# Debug.net
KiCad netlist of a schematic drawn in Altium Designer
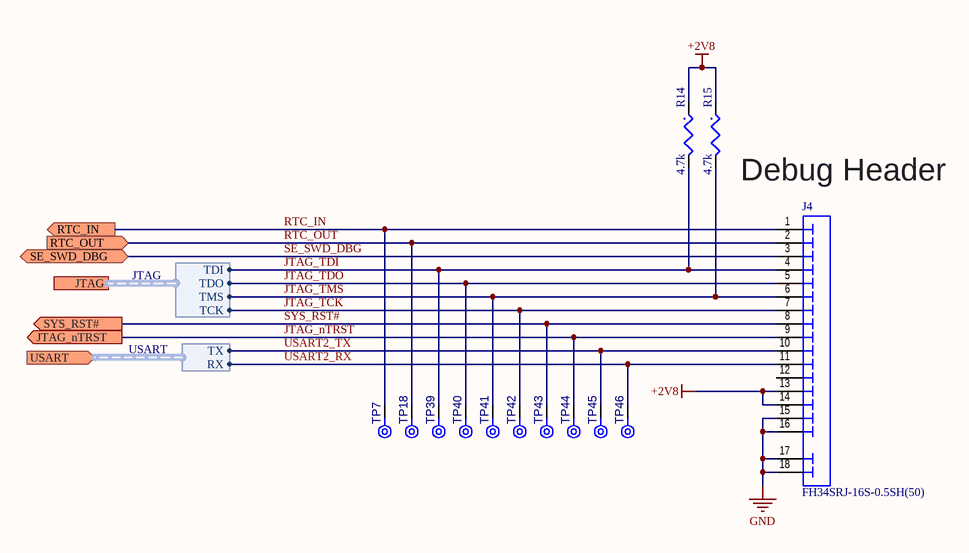
[diagram p0: Debug.SchDoc]

(export (version "E")
  (design (tool "Eeschema 10.0.6"))
  (components
    (comp (ref "J4")
      (value "FH34SRJ-16S-0.5SH(50)")
      (footprint "HIRO - FH34SRJ-16S-0.5SH_V")
      (libsource (lib "Altium Concord Pro on A365") (part "CN-FCC-16-2"))
    )
    (comp (ref "R14")
      (value "RES 4.7K 1/16W 1% 0402")
      (footprint "RESC0402(1005)_L")
      (description "4.7 kOhms ±1% 0.063W, 1/16W Chip Resistor 0402 (1005 Metric) Automotive AEC-Q200 Thick Film")
      (fields (field (name "RESISTANCE") "4.7k") (field (name "TOLERANCE") "1%"))
      (libsource (lib "Altium Concord Pro on A365") (part "RES-2"))
    )
    (comp (ref "R15")
      (value "RES 4.7K 1/16W 1% 0402")
      (footprint "RESC0402(1005)_L")
      (description "4.7 kOhms ±1% 0.063W, 1/16W Chip Resistor 0402 (1005 Metric) Automotive AEC-Q200 Thick Film")
      (fields (field (name "RESISTANCE") "4.7k") (field (name "TOLERANCE") "1%"))
      (libsource (lib "Altium Concord Pro on A365") (part "RES-2"))
    )
    (comp (ref "TP7")
      (value "TPAD8R")
      (footprint "TP08R")
      (description "0.8mm round")
      (libsource (lib "Altium Concord Pro on A365") (part "TP-R-1"))
    )
    (comp (ref "TP18")
      (value "TPAD8R")
      (footprint "TP08R")
      (description "0.8mm round")
      (libsource (lib "Altium Concord Pro on A365") (part "TP-R-1"))
    )
    (comp (ref "TP39")
      (value "TPAD8R")
      (footprint "TP08R")
      (description "0.8mm round")
      (libsource (lib "Altium Concord Pro on A365") (part "TP-R-1"))
    )
    (comp (ref "TP40")
      (value "TPAD8R")
      (footprint "TP08R")
      (description "0.8mm round")
      (libsource (lib "Altium Concord Pro on A365") (part "TP-R-1"))
    )
    (comp (ref "TP41")
      (value "TPAD8R")
      (footprint "TP08R")
      (description "0.8mm round")
      (libsource (lib "Altium Concord Pro on A365") (part "TP-R-1"))
    )
    (comp (ref "TP42")
      (value "TPAD8R")
      (footprint "TP08R")
      (description "0.8mm round")
      (libsource (lib "Altium Concord Pro on A365") (part "TP-R-1"))
    )
    (comp (ref "TP43")
      (value "TPAD8R")
      (footprint "TP08R")
      (description "0.8mm round")
      (libsource (lib "Altium Concord Pro on A365") (part "TP-R-1"))
    )
    (comp (ref "TP44")
      (value "TPAD8R")
      (footprint "TP08R")
      (description "0.8mm round")
      (libsource (lib "Altium Concord Pro on A365") (part "TP-R-1"))
    )
    (comp (ref "TP45")
      (value "TPAD8R")
      (footprint "TP08R")
      (description "0.8mm round")
      (libsource (lib "Altium Concord Pro on A365") (part "TP-R-1"))
    )
    (comp (ref "TP46")
      (value "TPAD8R")
      (footprint "TP08R")
      (description "0.8mm round")
      (libsource (lib "Altium Concord Pro on A365") (part "TP-R-1"))
    )
  )
  (nets
    (net (code "3") (name "+2V8") (class "Default")
      (node (ref "J4") (pin "13") (pinfunction "13_13") (pintype "passive"))
      (node (ref "J4") (pin "14") (pinfunction "14_14") (pintype "passive"))
      (node (ref "R14") (pin "1") (pinfunction "1_1") (pintype "passive"))
      (node (ref "R15") (pin "1") (pinfunction "1_1") (pintype "passive"))
    )
    (net (code "4") (name "/JTAG_TCK") (class "Default")
      (node (ref "J4") (pin "7") (pinfunction "7_7") (pintype "passive"))
      (node (ref "TP42") (pin "1") (pinfunction "TP_1") (pintype "passive"))
    )
    (net (code "5") (name "/JTAG_TDI") (class "Default")
      (node (ref "J4") (pin "4") (pinfunction "4_4") (pintype "passive"))
      (node (ref "R14") (pin "2") (pinfunction "2_2") (pintype "passive"))
      (node (ref "TP39") (pin "1") (pinfunction "TP_1") (pintype "passive"))
    )
    (net (code "6") (name "/JTAG_TDO") (class "Default")
      (node (ref "J4") (pin "5") (pinfunction "5_5") (pintype "passive"))
      (node (ref "TP40") (pin "1") (pinfunction "TP_1") (pintype "passive"))
    )
    (net (code "7") (name "/JTAG_TMS") (class "Default")
      (node (ref "J4") (pin "6") (pinfunction "6_6") (pintype "passive"))
      (node (ref "R15") (pin "2") (pinfunction "2_2") (pintype "passive"))
      (node (ref "TP41") (pin "1") (pinfunction "TP_1") (pintype "passive"))
    )
    (net (code "8") (name "/JTAG_nTRST") (class "Default")
      (node (ref "J4") (pin "9") (pinfunction "9_9") (pintype "passive"))
      (node (ref "TP44") (pin "1") (pinfunction "TP_1") (pintype "passive"))
    )
    (net (code "9") (name "/RTC_IN") (class "Default")
      (node (ref "J4") (pin "1") (pinfunction "1_1") (pintype "passive"))
      (node (ref "TP7") (pin "1") (pinfunction "TP_1") (pintype "passive"))
    )
    (net (code "10") (name "/RTC_OUT") (class "Default")
      (node (ref "J4") (pin "2") (pinfunction "2_2") (pintype "passive"))
      (node (ref "TP18") (pin "1") (pinfunction "TP_1") (pintype "passive"))
    )
    (net (code "11") (name "/SE_SWD_DBG") (class "Default")
      (node (ref "J4") (pin "3") (pinfunction "3_3") (pintype "passive"))
    )
    (net (code "12") (name "/SYS_RST#") (class "Default")
      (node (ref "J4") (pin "8") (pinfunction "8_8") (pintype "passive"))
      (node (ref "TP43") (pin "1") (pinfunction "TP_1") (pintype "passive"))
    )
    (net (code "13") (name "/USART2_RX") (class "Default")
      (node (ref "J4") (pin "11") (pinfunction "11_11") (pintype "passive"))
      (node (ref "TP46") (pin "1") (pinfunction "TP_1") (pintype "passive"))
    )
    (net (code "14") (name "/USART2_TX") (class "Default")
      (node (ref "J4") (pin "10") (pinfunction "10_10") (pintype "passive"))
      (node (ref "TP45") (pin "1") (pinfunction "TP_1") (pintype "passive"))
    )
    (net (code "17") (name "GND") (class "Default")
      (node (ref "J4") (pin "15") (pinfunction "15_15") (pintype "passive"))
      (node (ref "J4") (pin "16") (pinfunction "16_16") (pintype "passive"))
      (node (ref "J4") (pin "17") (pinfunction "17_17") (pintype "passive"))
      (node (ref "J4") (pin "18") (pinfunction "18_18") (pintype "passive"))
    )
    (net (code "18") (name "unconnected-(J4-Pad12)") (class "Default")
      (node (ref "J4") (pin "12") (pinfunction "12_12") (pintype "passive"))
    )
  )
)
